# RTx_Charger_Alternative.net
KiCad netlist of a schematic drawn in EAGLE
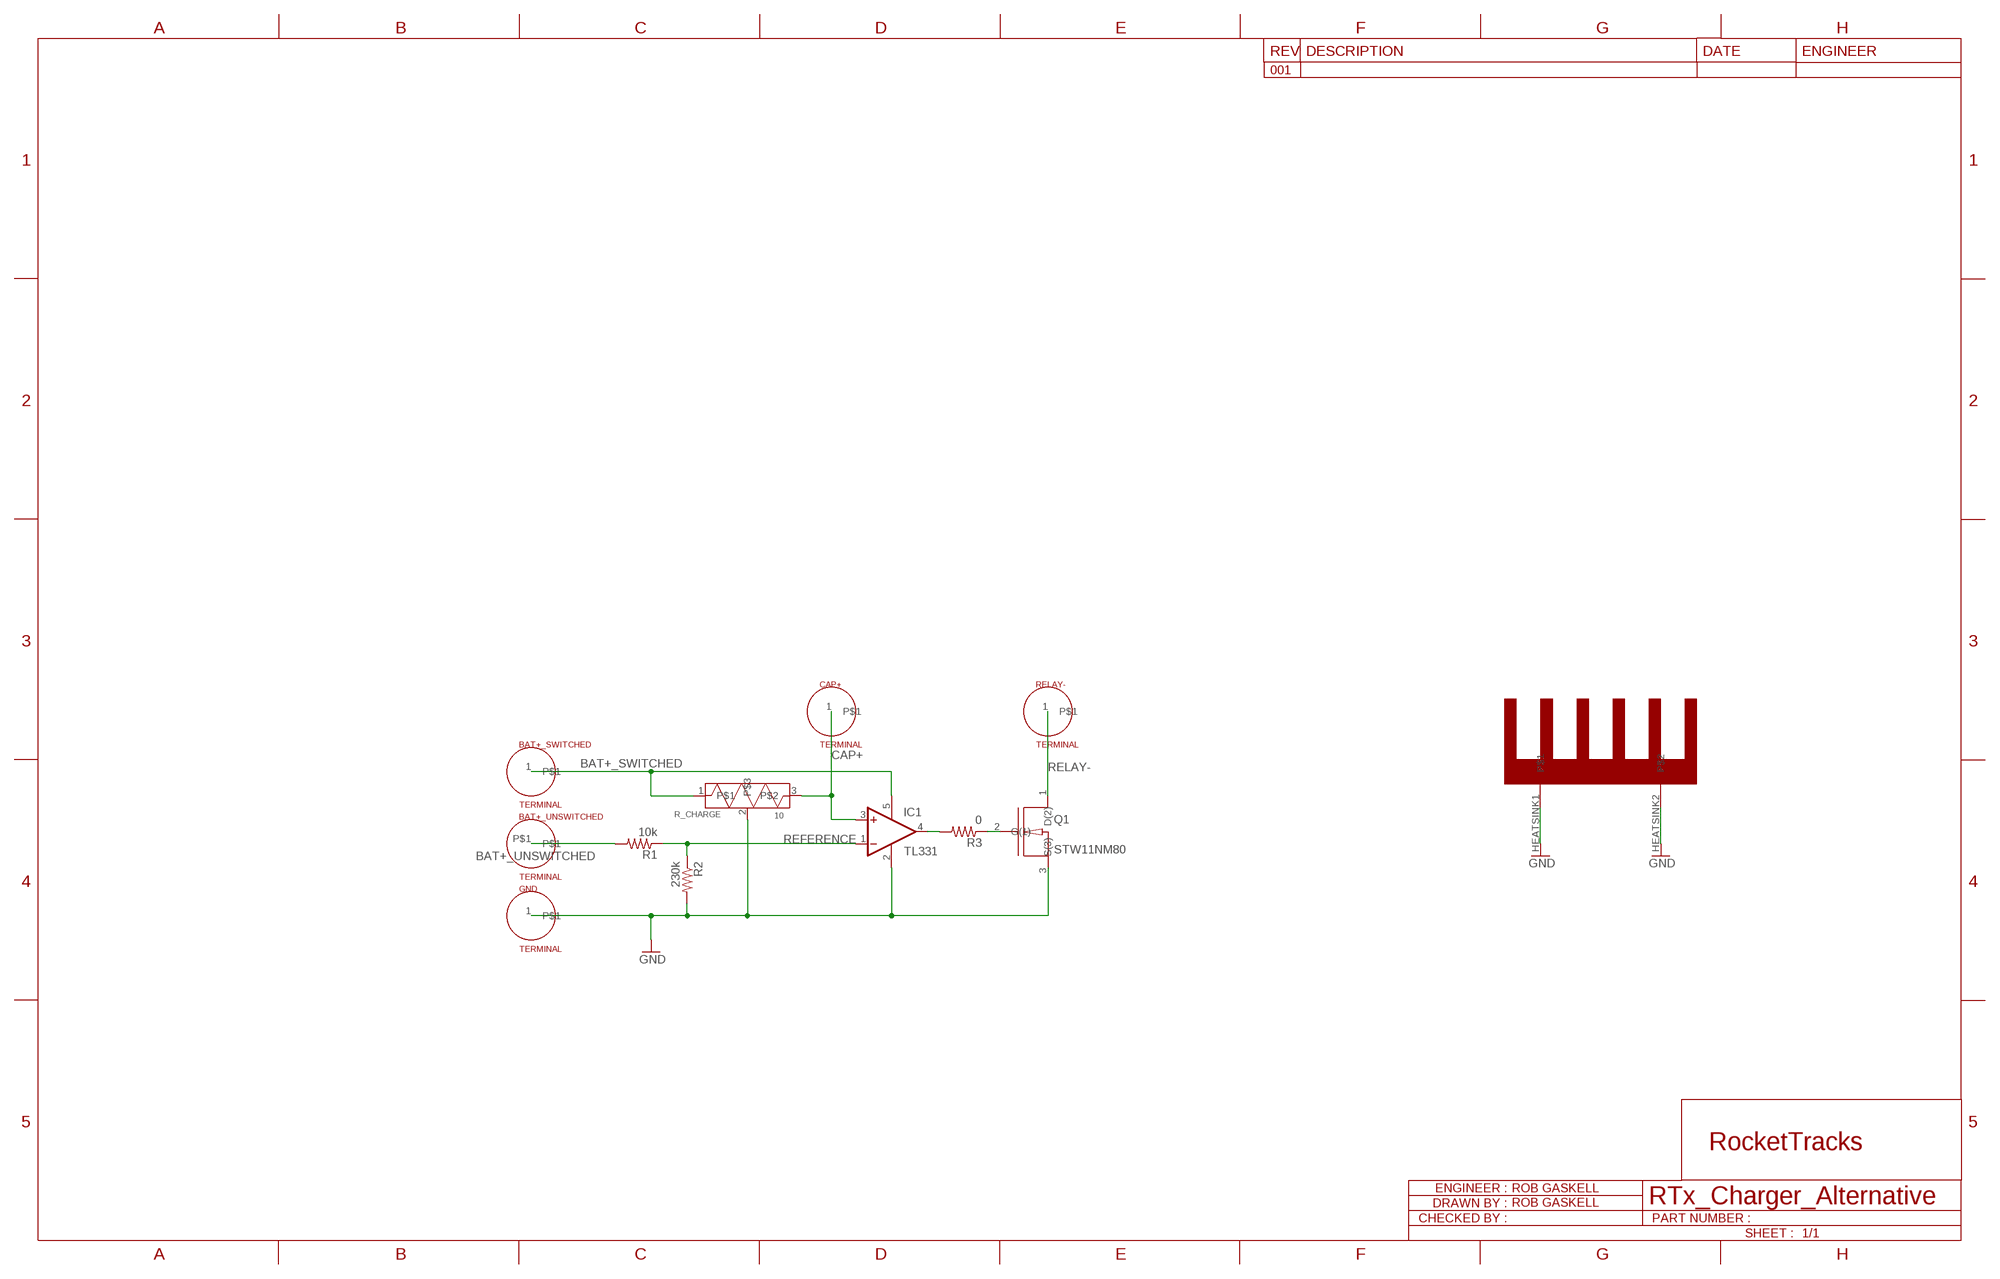
[diagram p0: schematic, sheet 1]

(export (version "E")
  (design (tool "Eeschema 10.0.6"))
  (components
    (comp (ref "BAT+_SWITCHED")
      (value "TERMINAL")
      (footprint "eagle-import:TERMINAL_BATTERY")
      (libsource (lib "eagle-import") (part "TERMINAL_BATTERY"))
    )
    (comp (ref "BAT+_UNSWITCHED")
      (value "TERMINAL")
      (footprint "eagle-import:TERMINAL_RELAY")
      (libsource (lib "eagle-import") (part "TERMINAL_RELAY"))
    )
    (comp (ref "CAP+")
      (value "TERMINAL")
      (footprint "eagle-import:TERMINAL_BATTERY")
      (libsource (lib "eagle-import") (part "TERMINAL_BATTERY"))
    )
    (comp (ref "GND")
      (value "TERMINAL")
      (footprint "eagle-import:TERMINAL_BATTERY")
      (libsource (lib "eagle-import") (part "TERMINAL_BATTERY"))
    )
    (comp (ref "HEATSINK")
      (value "WA-T247-101E")
      (footprint "eagle-import:WA-T247-101E")
      (libsource (lib "eagle-import") (part "WA-T247-101E"))
    )
    (comp (ref "IC1")
      (value "TL331")
      (footprint "eagle-import:DBV-R-PDSO-G5")
      (libsource (lib "eagle-import") (part "TL331"))
    )
    (comp (ref "Q1")
      (value "STW11NM80")
      (footprint "eagle-import:TO-247")
      (libsource (lib "eagle-import") (part "STW11NM80"))
    )
    (comp (ref "R1")
      (value "10k")
      (footprint "eagle-import:R1206")
      (libsource (lib "eagle-import") (part "R-US_R1206"))
    )
    (comp (ref "R2")
      (value "230k")
      (footprint "eagle-import:R1206")
      (libsource (lib "eagle-import") (part "R-US_R1206"))
    )
    (comp (ref "R3")
      (value "0")
      (footprint "eagle-import:R1206")
      (libsource (lib "eagle-import") (part "R-US_R1206"))
    )
    (comp (ref "RELAY-")
      (value "TERMINAL")
      (footprint "eagle-import:TERMINAL_BATTERY")
      (libsource (lib "eagle-import") (part "TERMINAL_BATTERY"))
    )
    (comp (ref "R_CHARGE")
      (value "10")
      (footprint "eagle-import:TEH70")
      (libsource (lib "eagle-import") (part "TEH70"))
    )
  )
  (nets
    (net (code "1") (name "/BAT+_SWITCHED") (class "Default")
      (node (ref "BAT+_SWITCHED") (pin "1") (pinfunction "P$1_1") (pintype "bidirectional"))
      (node (ref "IC1") (pin "5") (pinfunction "V+_5") (pintype "power_in"))
      (node (ref "R_CHARGE") (pin "1") (pinfunction "P$1_1") (pintype "bidirectional"))
    )
    (net (code "2") (name "/BAT+_UNSWITCHED") (class "Default")
      (node (ref "BAT+_UNSWITCHED") (pin "P$1") (pinfunction "P$1_P$1") (pintype "bidirectional"))
      (node (ref "R1") (pin "2") (pinfunction "2_2") (pintype "passive"))
    )
    (net (code "3") (name "/CAP+") (class "Default")
      (node (ref "CAP+") (pin "1") (pinfunction "P$1_1") (pintype "bidirectional"))
      (node (ref "IC1") (pin "3") (pinfunction "+IN_3") (pintype "input"))
      (node (ref "R_CHARGE") (pin "3") (pinfunction "P$2_3") (pintype "bidirectional"))
    )
    (net (code "4") (name "/REFERENCE") (class "Default")
      (node (ref "IC1") (pin "1") (pinfunction "-IN_1") (pintype "input"))
      (node (ref "R1") (pin "1") (pinfunction "1_1") (pintype "passive"))
      (node (ref "R2") (pin "1") (pinfunction "1_1") (pintype "passive"))
    )
    (net (code "5") (name "/RELAY-") (class "Default")
      (node (ref "Q1") (pin "1") (pinfunction "D(2)_1") (pintype "bidirectional"))
      (node (ref "RELAY-") (pin "1") (pinfunction "P$1_1") (pintype "bidirectional"))
    )
    (net (code "6") (name "GND") (class "Default")
      (node (ref "GND") (pin "1") (pinfunction "P$1_1") (pintype "bidirectional"))
      (node (ref "HEATSINK") (pin "HEATSINK1") (pinfunction "P$1_HEATSINK1") (pintype "bidirectional"))
      (node (ref "HEATSINK") (pin "HEATSINK2") (pinfunction "P$2_HEATSINK2") (pintype "bidirectional"))
      (node (ref "IC1") (pin "2") (pinfunction "GND_2") (pintype "power_in"))
      (node (ref "Q1") (pin "3") (pinfunction "S(3)_3") (pintype "bidirectional"))
      (node (ref "R2") (pin "2") (pinfunction "2_2") (pintype "passive"))
      (node (ref "R_CHARGE") (pin "2") (pinfunction "P$3_2") (pintype "power_in"))
    )
    (net (code "7") (name "Net-(IC1-OUT)") (class "Default")
      (node (ref "IC1") (pin "4") (pinfunction "OUT_4") (pintype "output"))
      (node (ref "R3") (pin "2") (pinfunction "2_2") (pintype "passive"))
    )
    (net (code "8") (name "Net-(Q1-G(1))") (class "Default")
      (node (ref "Q1") (pin "2") (pinfunction "G(1)_2") (pintype "bidirectional"))
      (node (ref "R3") (pin "1") (pinfunction "1_1") (pintype "passive"))
    )
  )
)
